# current_sensor.net
KiCad netlist of a schematic drawn in EAGLE
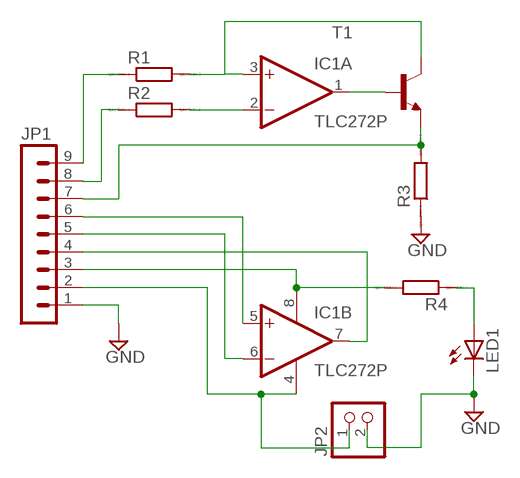
[diagram p0: schematic, sheet 1]

(export (version "E")
  (design (tool "Eeschema 10.0.6"))
  (components
    (comp (ref "IC1")
      (value "TLC272P")
      (footprint "eagle-import:DIL08")
      (libsource (lib "eagle-import") (part "TLC272P"))
    )
    (comp (ref "JP1")
      (value "MA09-1")
      (footprint "eagle-import:MA09-1")
      (libsource (lib "eagle-import") (part "MA09-1"))
    )
    (comp (ref "JP2")
      (value "PINHD-1X2")
      (footprint "eagle-import:1X02")
      (libsource (lib "eagle-import") (part "PINHD-1X2"))
    )
    (comp (ref "LED1")
      (value "LEDCHIP-LED0805")
      (footprint "eagle-import:CHIP-LED0805")
      (libsource (lib "eagle-import") (part "LEDCHIP-LED0805"))
    )
    (comp (ref "R1") (value "R") (footprint "eagle-import:R0805") (libsource (lib "eagle-import") (part "R")))
    (comp (ref "R2") (value "R") (footprint "eagle-import:R0805") (libsource (lib "eagle-import") (part "R")))
    (comp (ref "R3") (value "R") (footprint "eagle-import:R0805") (libsource (lib "eagle-import") (part "R")))
    (comp (ref "R4") (value "R") (footprint "eagle-import:R0805") (libsource (lib "eagle-import") (part "R")))
    (comp (ref "T1")
      (value "BF422-NPN-TO92-BCE")
      (footprint "eagle-import:TO92-BCE")
      (libsource (lib "eagle-import") (part "-NPN-TO92-BCEBF422"))
    )
  )
  (nets
    (net (code "1") (name "GND") (class "Default")
      (node (ref "JP1") (pin "1") (pinfunction "1_1") (pintype "passive"))
      (node (ref "JP2") (pin "2") (pinfunction "2_2") (pintype "passive"))
      (node (ref "LED1") (pin "C") (pinfunction "C_C") (pintype "passive"))
      (node (ref "R3") (pin "1") (pinfunction "1_1") (pintype "passive"))
    )
    (net (code "2") (name "Net-(IC1A-+IN)") (class "Default")
      (node (ref "IC1") (pin "3") (pinfunction "+IN_3") (pintype "input"))
      (node (ref "R1") (pin "2") (pinfunction "2_2") (pintype "passive"))
      (node (ref "T1") (pin "C") (pinfunction "C_C") (pintype "passive"))
    )
    (net (code "3") (name "Net-(IC1A--IN)") (class "Default")
      (node (ref "IC1") (pin "2") (pinfunction "-IN_2") (pintype "input"))
      (node (ref "R2") (pin "2") (pinfunction "2_2") (pintype "passive"))
    )
    (net (code "4") (name "Net-(IC1A-OUT)") (class "Default")
      (node (ref "IC1") (pin "1") (pinfunction "OUT_1") (pintype "output"))
      (node (ref "T1") (pin "B") (pinfunction "B_B") (pintype "passive"))
    )
    (net (code "5") (name "Net-(IC1B-+IN)") (class "Default")
      (node (ref "IC1") (pin "5") (pinfunction "+IN_5") (pintype "input"))
      (node (ref "JP1") (pin "6") (pinfunction "6_6") (pintype "passive"))
    )
    (net (code "6") (name "Net-(IC1B--IN)") (class "Default")
      (node (ref "IC1") (pin "6") (pinfunction "-IN_6") (pintype "input"))
      (node (ref "JP1") (pin "5") (pinfunction "5_5") (pintype "passive"))
    )
    (net (code "7") (name "Net-(IC1B-OUT)") (class "Default")
      (node (ref "IC1") (pin "7") (pinfunction "OUT_7") (pintype "output"))
      (node (ref "JP1") (pin "4") (pinfunction "4_4") (pintype "passive"))
    )
    (net (code "8") (name "Net-(IC1C-V+)") (class "Default")
      (node (ref "IC1") (pin "8") (pinfunction "V+_8") (pintype "power_in"))
      (node (ref "JP1") (pin "3") (pinfunction "3_3") (pintype "passive"))
      (node (ref "R4") (pin "2") (pinfunction "2_2") (pintype "passive"))
    )
    (net (code "9") (name "Net-(IC1C-V-)") (class "Default")
      (node (ref "IC1") (pin "4") (pinfunction "V-_4") (pintype "power_in"))
      (node (ref "JP1") (pin "2") (pinfunction "2_2") (pintype "passive"))
      (node (ref "JP2") (pin "1") (pinfunction "1_1") (pintype "passive"))
    )
    (net (code "10") (name "Net-(JP1-Pad7)") (class "Default")
      (node (ref "JP1") (pin "7") (pinfunction "7_7") (pintype "passive"))
      (node (ref "R3") (pin "2") (pinfunction "2_2") (pintype "passive"))
      (node (ref "T1") (pin "E") (pinfunction "E_E") (pintype "passive"))
    )
    (net (code "11") (name "Net-(JP1-Pad8)") (class "Default")
      (node (ref "JP1") (pin "8") (pinfunction "8_8") (pintype "passive"))
      (node (ref "R2") (pin "1") (pinfunction "1_1") (pintype "passive"))
    )
    (net (code "12") (name "Net-(JP1-Pad9)") (class "Default")
      (node (ref "JP1") (pin "9") (pinfunction "9_9") (pintype "passive"))
      (node (ref "R1") (pin "1") (pinfunction "1_1") (pintype "passive"))
    )
    (net (code "13") (name "Net-(LED1-PadA)") (class "Default")
      (node (ref "LED1") (pin "A") (pinfunction "A_A") (pintype "passive"))
      (node (ref "R4") (pin "1") (pinfunction "1_1") (pintype "passive"))
    )
  )
)
